# Optisk_ut.net
KiCad netlist of a schematic drawn in Altium Designer
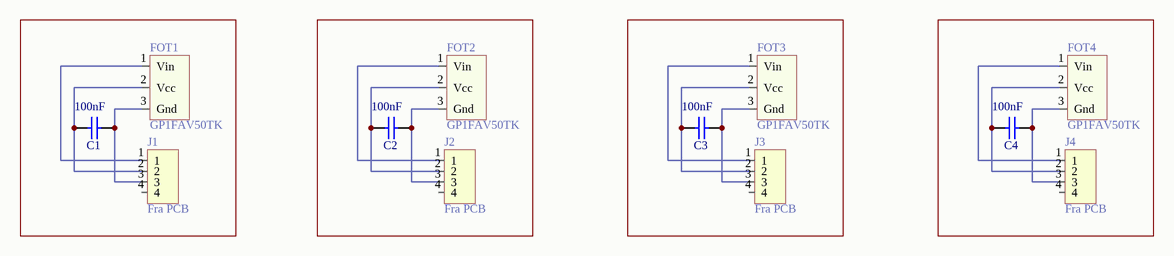
[diagram p0: Optisk_ut.SchDoc]

(export (version "E")
  (design (tool "Eeschema 10.0.6"))
  (components
    (comp (ref "C1")
      (value "100nF")
      (footprint "CAPC0805(2012)100_L")
      (description "CAP 100nF 50V ±5% 0805 (2012 Metric) Thickness 1mm SMD")
      (fields (field (name "TOLERANCE") "±5%"))
      (libsource (lib "Altium Content Vault") (part "CMP-1036-04418-1"))
    )
    (comp (ref "C2")
      (value "100nF")
      (footprint "CAPC0805(2012)100_L")
      (description "CAP 100nF 50V ±5% 0805 (2012 Metric) Thickness 1mm SMD")
      (fields (field (name "TOLERANCE") "±5%"))
      (libsource (lib "Altium Content Vault") (part "CMP-1036-04418-1"))
    )
    (comp (ref "C3")
      (value "100nF")
      (footprint "CAPC0805(2012)100_L")
      (description "CAP 100nF 50V ±5% 0805 (2012 Metric) Thickness 1mm SMD")
      (fields (field (name "TOLERANCE") "±5%"))
      (libsource (lib "Altium Content Vault") (part "CMP-1036-04418-1"))
    )
    (comp (ref "C4")
      (value "100nF")
      (footprint "CAPC0805(2012)100_L")
      (description "CAP 100nF 50V ±5% 0805 (2012 Metric) Thickness 1mm SMD")
      (fields (field (name "TOLERANCE") "±5%"))
      (libsource (lib "Altium Content Vault") (part "CMP-1036-04418-1"))
    )
    (comp (ref "FOT1")
      (value "GP1FAV50TK")
      (footprint "GP1FAV50TK")
      (libsource (lib "Schlib1") (part "GP1FAV50TK"))
    )
    (comp (ref "FOT2")
      (value "GP1FAV50TK")
      (footprint "GP1FAV50TK")
      (libsource (lib "Schlib1") (part "GP1FAV50TK"))
    )
    (comp (ref "FOT3")
      (value "GP1FAV50TK")
      (footprint "GP1FAV50TK")
      (libsource (lib "Schlib1") (part "GP1FAV50TK"))
    )
    (comp (ref "FOT4")
      (value "GP1FAV50TK")
      (footprint "GP1FAV50TK")
      (libsource (lib "Schlib1") (part "GP1FAV50TK"))
    )
    (comp (ref "J1") (value "Fra PCB") (footprint "JST 4pin") (libsource (lib "Schlib1") (part "JST 4pin")))
    (comp (ref "J2") (value "Fra PCB") (footprint "JST 4pin") (libsource (lib "Schlib1") (part "JST 4pin")))
    (comp (ref "J3") (value "Fra PCB") (footprint "JST 4pin") (libsource (lib "Schlib1") (part "JST 4pin")))
    (comp (ref "J4") (value "Fra PCB") (footprint "JST 4pin") (libsource (lib "Schlib1") (part "JST 4pin")))
  )
  (nets
    (net (code "1") (name "Net-(FOT1-Gnd)") (class "Default")
      (node (ref "C1") (pin "2") (pinfunction "2_2") (pintype "passive"))
      (node (ref "FOT1") (pin "3") (pinfunction "Gnd_3") (pintype "passive"))
      (node (ref "J1") (pin "3") (pinfunction "3_3") (pintype "passive"))
    )
    (net (code "2") (name "Net-(FOT1-Vcc)") (class "Default")
      (node (ref "C1") (pin "1") (pinfunction "1_1") (pintype "passive"))
      (node (ref "FOT1") (pin "2") (pinfunction "Vcc_2") (pintype "passive"))
      (node (ref "J1") (pin "2") (pinfunction "2_2") (pintype "passive"))
    )
    (net (code "3") (name "Net-(FOT1-Vin)") (class "Default")
      (node (ref "FOT1") (pin "1") (pinfunction "Vin_1") (pintype "passive"))
      (node (ref "J1") (pin "1") (pinfunction "1_1") (pintype "passive"))
    )
    (net (code "4") (name "Net-(FOT2-Gnd)") (class "Default")
      (node (ref "C2") (pin "2") (pinfunction "2_2") (pintype "passive"))
      (node (ref "FOT2") (pin "3") (pinfunction "Gnd_3") (pintype "passive"))
      (node (ref "J2") (pin "3") (pinfunction "3_3") (pintype "passive"))
    )
    (net (code "5") (name "Net-(FOT2-Vcc)") (class "Default")
      (node (ref "C2") (pin "1") (pinfunction "1_1") (pintype "passive"))
      (node (ref "FOT2") (pin "2") (pinfunction "Vcc_2") (pintype "passive"))
      (node (ref "J2") (pin "2") (pinfunction "2_2") (pintype "passive"))
    )
    (net (code "6") (name "Net-(FOT2-Vin)") (class "Default")
      (node (ref "FOT2") (pin "1") (pinfunction "Vin_1") (pintype "passive"))
      (node (ref "J2") (pin "1") (pinfunction "1_1") (pintype "passive"))
    )
    (net (code "7") (name "Net-(FOT3-Gnd)") (class "Default")
      (node (ref "C3") (pin "2") (pinfunction "2_2") (pintype "passive"))
      (node (ref "FOT3") (pin "3") (pinfunction "Gnd_3") (pintype "passive"))
      (node (ref "J3") (pin "3") (pinfunction "3_3") (pintype "passive"))
    )
    (net (code "8") (name "Net-(FOT3-Vcc)") (class "Default")
      (node (ref "C3") (pin "1") (pinfunction "1_1") (pintype "passive"))
      (node (ref "FOT3") (pin "2") (pinfunction "Vcc_2") (pintype "passive"))
      (node (ref "J3") (pin "2") (pinfunction "2_2") (pintype "passive"))
    )
    (net (code "9") (name "Net-(FOT3-Vin)") (class "Default")
      (node (ref "FOT3") (pin "1") (pinfunction "Vin_1") (pintype "passive"))
      (node (ref "J3") (pin "1") (pinfunction "1_1") (pintype "passive"))
    )
    (net (code "10") (name "Net-(FOT4-Gnd)") (class "Default")
      (node (ref "C4") (pin "2") (pinfunction "2_2") (pintype "passive"))
      (node (ref "FOT4") (pin "3") (pinfunction "Gnd_3") (pintype "passive"))
      (node (ref "J4") (pin "3") (pinfunction "3_3") (pintype "passive"))
    )
    (net (code "11") (name "Net-(FOT4-Vcc)") (class "Default")
      (node (ref "C4") (pin "1") (pinfunction "1_1") (pintype "passive"))
      (node (ref "FOT4") (pin "2") (pinfunction "Vcc_2") (pintype "passive"))
      (node (ref "J4") (pin "2") (pinfunction "2_2") (pintype "passive"))
    )
    (net (code "12") (name "Net-(FOT4-Vin)") (class "Default")
      (node (ref "FOT4") (pin "1") (pinfunction "Vin_1") (pintype "passive"))
      (node (ref "J4") (pin "1") (pinfunction "1_1") (pintype "passive"))
    )
    (net (code "13") (name "unconnected-(J1-Pad4)") (class "Default")
      (node (ref "J1") (pin "4") (pinfunction "4_4") (pintype "passive"))
    )
    (net (code "14") (name "unconnected-(J2-Pad4)") (class "Default")
      (node (ref "J2") (pin "4") (pinfunction "4_4") (pintype "passive"))
    )
    (net (code "15") (name "unconnected-(J3-Pad4)") (class "Default")
      (node (ref "J3") (pin "4") (pinfunction "4_4") (pintype "passive"))
    )
    (net (code "16") (name "unconnected-(J4-Pad4)") (class "Default")
      (node (ref "J4") (pin "4") (pinfunction "4_4") (pintype "passive"))
    )
  )
)
